# USB-Audio_ver_1_0.net
KiCad netlist of a schematic drawn in EAGLE
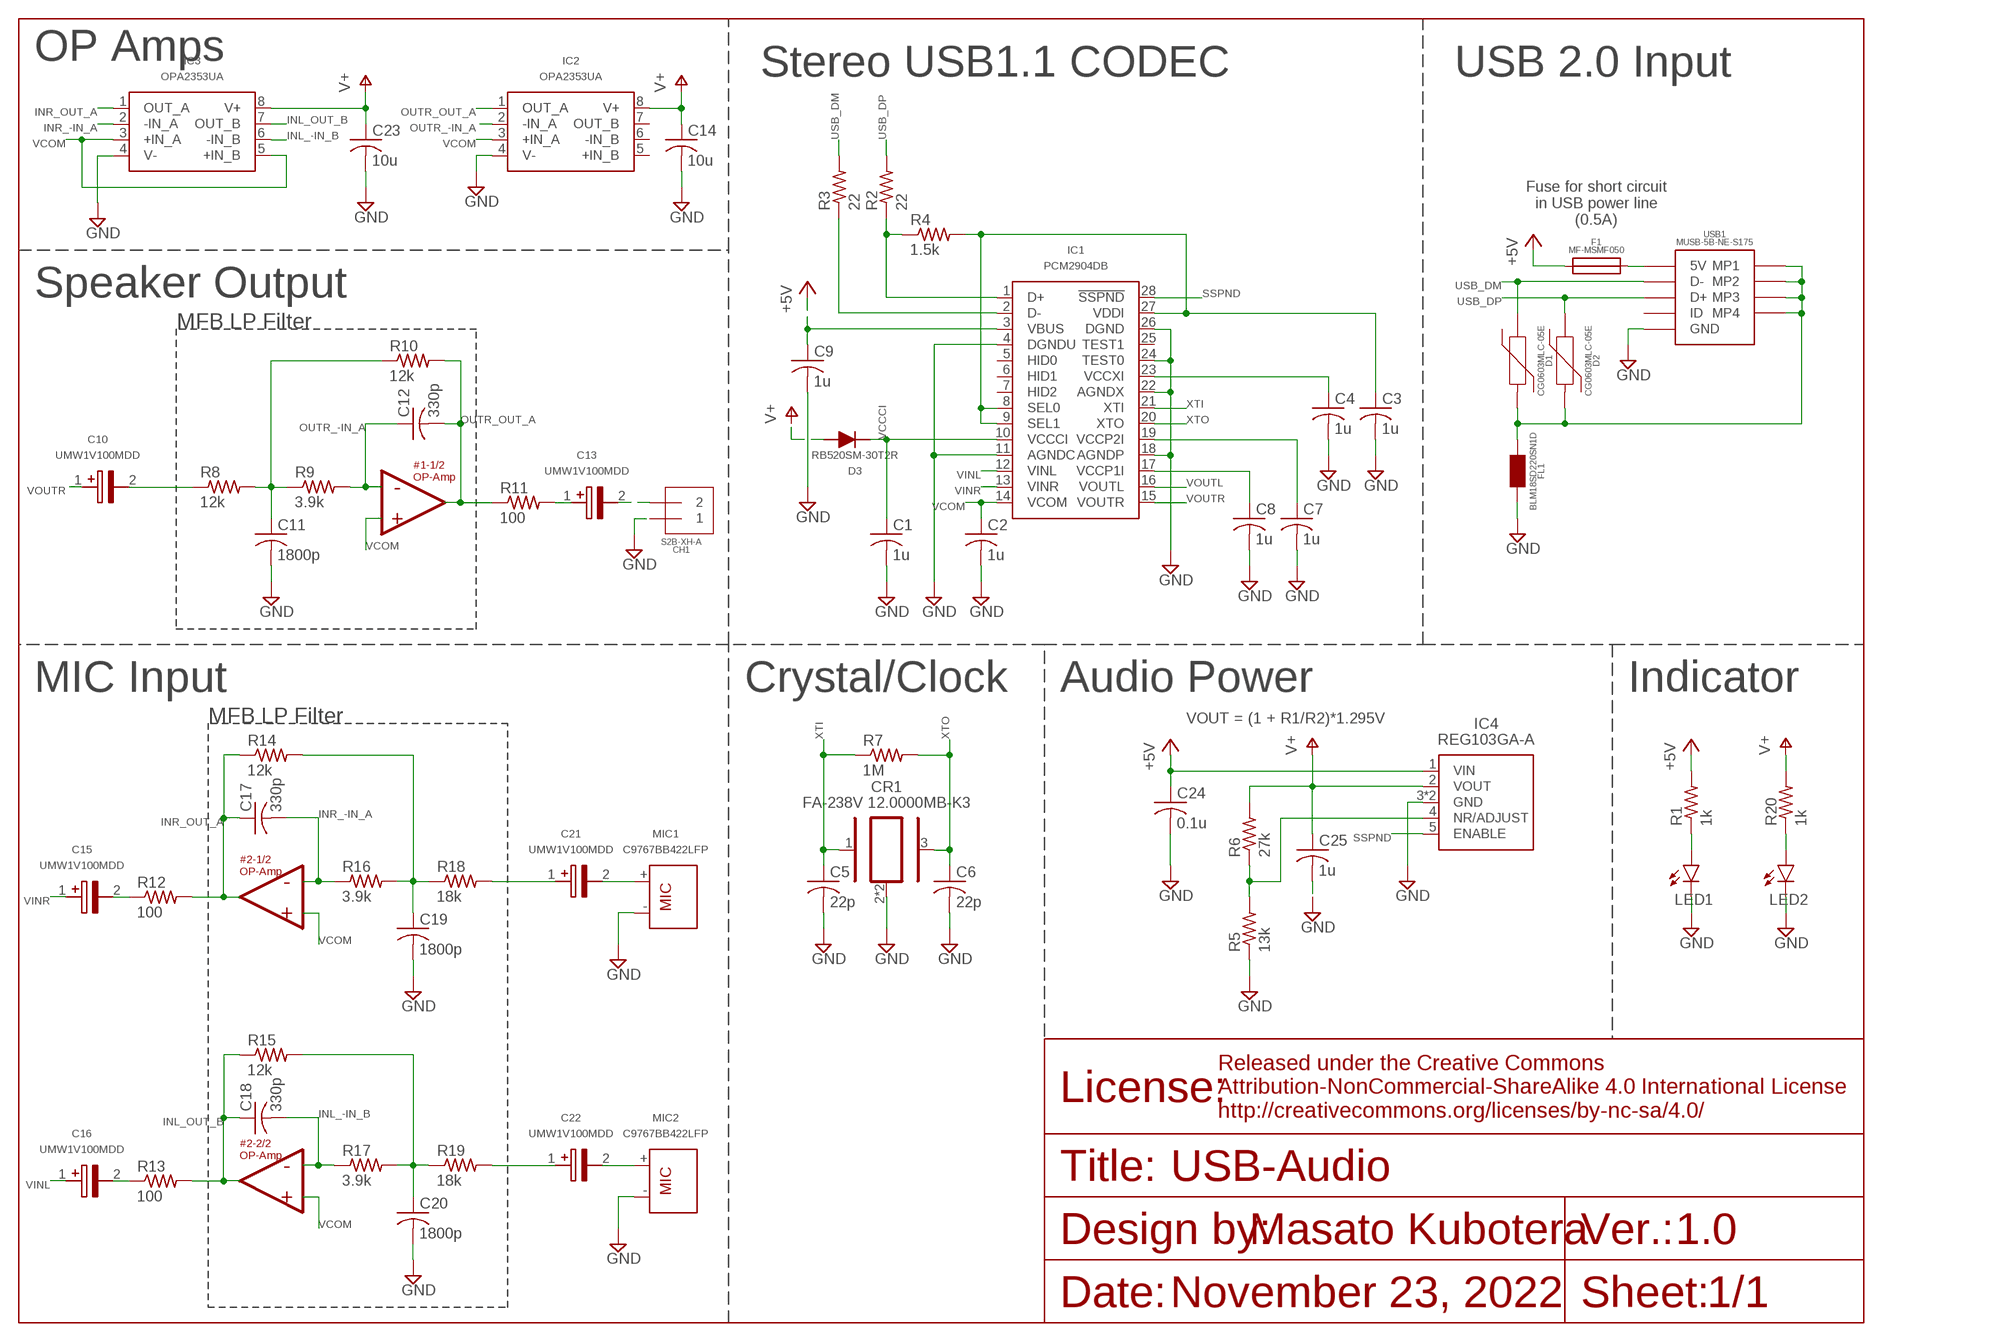
[diagram p0: schematic, sheet 1]

(export (version "E")
  (design (tool "Eeschema 10.0.6"))
  (components
    (comp (ref "C1")
      (value "1u")
      (footprint "eagle-import:C1608")
      (libsource (lib "eagle-import") (part "C-USC1608"))
    )
    (comp (ref "C2")
      (value "1u")
      (footprint "eagle-import:C1608")
      (libsource (lib "eagle-import") (part "C-USC1608"))
    )
    (comp (ref "C3")
      (value "1u")
      (footprint "eagle-import:C1608")
      (libsource (lib "eagle-import") (part "C-USC1608"))
    )
    (comp (ref "C4")
      (value "1u")
      (footprint "eagle-import:C1608")
      (libsource (lib "eagle-import") (part "C-USC1608"))
    )
    (comp (ref "C5")
      (value "22p")
      (footprint "eagle-import:C1608")
      (libsource (lib "eagle-import") (part "C-USC1608"))
    )
    (comp (ref "C6")
      (value "22p")
      (footprint "eagle-import:C1608")
      (libsource (lib "eagle-import") (part "C-USC1608"))
    )
    (comp (ref "C7")
      (value "1u")
      (footprint "eagle-import:C1608")
      (libsource (lib "eagle-import") (part "C-USC1608"))
    )
    (comp (ref "C8")
      (value "1u")
      (footprint "eagle-import:C1608")
      (libsource (lib "eagle-import") (part "C-USC1608"))
    )
    (comp (ref "C9")
      (value "1u")
      (footprint "eagle-import:C1608")
      (libsource (lib "eagle-import") (part "C-USC1608"))
    )
    (comp (ref "C10")
      (value "UMW1V100MDD")
      (footprint "eagle-import:UMW1V100MDD")
      (libsource (lib "eagle-import") (part "UMW1V100MDD"))
    )
    (comp (ref "C11")
      (value "1800p")
      (footprint "eagle-import:C1608")
      (libsource (lib "eagle-import") (part "C-USC1608"))
    )
    (comp (ref "C12")
      (value "330p")
      (footprint "eagle-import:C1608")
      (libsource (lib "eagle-import") (part "C-USC1608"))
    )
    (comp (ref "C13")
      (value "UMW1V100MDD")
      (footprint "eagle-import:UMW1V100MDD")
      (libsource (lib "eagle-import") (part "UMW1V100MDD"))
    )
    (comp (ref "C14")
      (value "10u")
      (footprint "eagle-import:C1608")
      (libsource (lib "eagle-import") (part "C-USC1608"))
    )
    (comp (ref "C15")
      (value "UMW1V100MDD")
      (footprint "eagle-import:UMW1V100MDD")
      (libsource (lib "eagle-import") (part "UMW1V100MDD"))
    )
    (comp (ref "C16")
      (value "UMW1V100MDD")
      (footprint "eagle-import:UMW1V100MDD")
      (libsource (lib "eagle-import") (part "UMW1V100MDD"))
    )
    (comp (ref "C17")
      (value "330p")
      (footprint "eagle-import:C1608")
      (libsource (lib "eagle-import") (part "C-USC1608"))
    )
    (comp (ref "C18")
      (value "330p")
      (footprint "eagle-import:C1608")
      (libsource (lib "eagle-import") (part "C-USC1608"))
    )
    (comp (ref "C19")
      (value "1800p")
      (footprint "eagle-import:C1608")
      (libsource (lib "eagle-import") (part "C-USC1608"))
    )
    (comp (ref "C20")
      (value "1800p")
      (footprint "eagle-import:C1608")
      (libsource (lib "eagle-import") (part "C-USC1608"))
    )
    (comp (ref "C21")
      (value "UMW1V100MDD")
      (footprint "eagle-import:UMW1V100MDD")
      (libsource (lib "eagle-import") (part "UMW1V100MDD"))
    )
    (comp (ref "C22")
      (value "UMW1V100MDD")
      (footprint "eagle-import:UMW1V100MDD")
      (libsource (lib "eagle-import") (part "UMW1V100MDD"))
    )
    (comp (ref "C23")
      (value "10u")
      (footprint "eagle-import:C1608")
      (libsource (lib "eagle-import") (part "C-USC1608"))
    )
    (comp (ref "C24")
      (value "0.1u")
      (footprint "eagle-import:C1608")
      (libsource (lib "eagle-import") (part "C-USC1608"))
    )
    (comp (ref "C25")
      (value "1u")
      (footprint "eagle-import:C1608")
      (libsource (lib "eagle-import") (part "C-USC1608"))
    )
    (comp (ref "CH1")
      (value "S2B-XH-A")
      (footprint "eagle-import:S2B-XH-A")
      (libsource (lib "eagle-import") (part "S2B-XH-A"))
    )
    (comp (ref "CR1")
      (value "FA-238V12.0000MB-K3")
      (footprint "eagle-import:FA238V")
      (libsource (lib "eagle-import") (part "FA-238V12.0000MB-K3"))
    )
    (comp (ref "D1")
      (value "CG0603MLC-05E")
      (footprint "eagle-import:CG0603MLC-05E")
      (libsource (lib "eagle-import") (part "CG0603MLC-05E"))
    )
    (comp (ref "D2")
      (value "CG0603MLC-05E")
      (footprint "eagle-import:CG0603MLC-05E")
      (libsource (lib "eagle-import") (part "CG0603MLC-05E"))
    )
    (comp (ref "D3")
      (value "RB520SM-30T2R")
      (footprint "eagle-import:SOD-523-2")
      (libsource (lib "eagle-import") (part "RB520SM-30T2R"))
    )
    (comp (ref "F1")
      (value "MF-MSMF050")
      (footprint "eagle-import:MF-MSMF050")
      (libsource (lib "eagle-import") (part "MF-MSMF050"))
    )
    (comp (ref "FL1")
      (value "BLM18SD220SN1D")
      (footprint "eagle-import:BLM18SD220SN1D")
      (libsource (lib "eagle-import") (part "BLM18SD220SN1D"))
    )
    (comp (ref "IC1")
      (value "PCM2904DB")
      (footprint "eagle-import:PCM2904DB")
      (libsource (lib "eagle-import") (part "PCM2904DB"))
    )
    (comp (ref "IC2")
      (value "OPA2353UA")
      (footprint "eagle-import:OPA2353UA")
      (libsource (lib "eagle-import") (part "OPA2353UA"))
    )
    (comp (ref "IC3")
      (value "OPA2353UA")
      (footprint "eagle-import:OPA2353UA")
      (libsource (lib "eagle-import") (part "OPA2353UA"))
    )
    (comp (ref "IC4")
      (value "REG103GA-A")
      (footprint "eagle-import:SOT223-5")
      (libsource (lib "eagle-import") (part "REG103GA-A"))
    )
    (comp (ref "LED1")
      (value "LEDSML0603")
      (footprint "eagle-import:SML0603")
      (libsource (lib "eagle-import") (part "LEDSML0603"))
    )
    (comp (ref "LED2")
      (value "LEDSML0603")
      (footprint "eagle-import:SML0603")
      (libsource (lib "eagle-import") (part "LEDSML0603"))
    )
    (comp (ref "MIC1")
      (value "C9767BB422LFP")
      (footprint "eagle-import:C9767BB422LFP")
      (libsource (lib "eagle-import") (part "C9767BB422LFP"))
    )
    (comp (ref "MIC2")
      (value "C9767BB422LFP")
      (footprint "eagle-import:C9767BB422LFP")
      (libsource (lib "eagle-import") (part "C9767BB422LFP"))
    )
    (comp (ref "R1")
      (value "1k")
      (footprint "eagle-import:R0603")
      (libsource (lib "eagle-import") (part "R-US_R0603"))
    )
    (comp (ref "R2")
      (value "22")
      (footprint "eagle-import:R0603")
      (libsource (lib "eagle-import") (part "R-US_R0603"))
    )
    (comp (ref "R3")
      (value "22")
      (footprint "eagle-import:R0603")
      (libsource (lib "eagle-import") (part "R-US_R0603"))
    )
    (comp (ref "R4")
      (value "1.5k")
      (footprint "eagle-import:R0603")
      (libsource (lib "eagle-import") (part "R-US_R0603"))
    )
    (comp (ref "R5")
      (value "13k")
      (footprint "eagle-import:R0603")
      (libsource (lib "eagle-import") (part "R-US_R0603"))
    )
    (comp (ref "R6")
      (value "27k")
      (footprint "eagle-import:R0603")
      (libsource (lib "eagle-import") (part "R-US_R0603"))
    )
    (comp (ref "R7")
      (value "1M")
      (footprint "eagle-import:R0603")
      (libsource (lib "eagle-import") (part "R-US_R0603"))
    )
    (comp (ref "R8")
      (value "12k")
      (footprint "eagle-import:R0603")
      (libsource (lib "eagle-import") (part "R-US_R0603"))
    )
    (comp (ref "R9")
      (value "3.9k")
      (footprint "eagle-import:R0603")
      (libsource (lib "eagle-import") (part "R-US_R0603"))
    )
    (comp (ref "R10")
      (value "12k")
      (footprint "eagle-import:R0603")
      (libsource (lib "eagle-import") (part "R-US_R0603"))
    )
    (comp (ref "R11")
      (value "100")
      (footprint "eagle-import:R0603")
      (libsource (lib "eagle-import") (part "R-US_R0603"))
    )
    (comp (ref "R12")
      (value "100")
      (footprint "eagle-import:R0603")
      (libsource (lib "eagle-import") (part "R-US_R0603"))
    )
    (comp (ref "R13")
      (value "100")
      (footprint "eagle-import:R0603")
      (libsource (lib "eagle-import") (part "R-US_R0603"))
    )
    (comp (ref "R14")
      (value "12k")
      (footprint "eagle-import:R0603")
      (libsource (lib "eagle-import") (part "R-US_R0603"))
    )
    (comp (ref "R15")
      (value "12k")
      (footprint "eagle-import:R0603")
      (libsource (lib "eagle-import") (part "R-US_R0603"))
    )
    (comp (ref "R16")
      (value "3.9k")
      (footprint "eagle-import:R0603")
      (libsource (lib "eagle-import") (part "R-US_R0603"))
    )
    (comp (ref "R17")
      (value "3.9k")
      (footprint "eagle-import:R0603")
      (libsource (lib "eagle-import") (part "R-US_R0603"))
    )
    (comp (ref "R18")
      (value "18k")
      (footprint "eagle-import:R0603")
      (libsource (lib "eagle-import") (part "R-US_R0603"))
    )
    (comp (ref "R19")
      (value "18k")
      (footprint "eagle-import:R0603")
      (libsource (lib "eagle-import") (part "R-US_R0603"))
    )
    (comp (ref "R20")
      (value "1k")
      (footprint "eagle-import:R0603")
      (libsource (lib "eagle-import") (part "R-US_R0603"))
    )
    (comp (ref "USB1")
      (value "MINI_USB_B_SMD")
      (footprint "eagle-import:MINI_USB_B_SMD")
      (libsource (lib "eagle-import") (part "MINI_USB_B_SMD"))
    )
  )
  (nets
    (net (code "1") (name "+5V") (class "Default")
      (node (ref "C24") (pin "1") (pinfunction "1_1") (pintype "passive"))
      (node (ref "C9") (pin "1") (pinfunction "1_1") (pintype "passive"))
      (node (ref "F1") (pin "1") (pinfunction "1_1") (pintype "bidirectional"))
      (node (ref "IC1") (pin "3") (pinfunction "VBUS_3") (pintype "bidirectional"))
      (node (ref "IC4") (pin "1") (pinfunction "VIN_1") (pintype "input"))
      (node (ref "R1") (pin "2") (pinfunction "2_2") (pintype "passive"))
    )
    (net (code "2") (name "/INL_-IN_B") (class "Default")
      (node (ref "C18") (pin "2") (pinfunction "2_2") (pintype "passive"))
      (node (ref "IC3") (pin "6") (pinfunction "-IN_B_6") (pintype "bidirectional"))
      (node (ref "R17") (pin "1") (pinfunction "1_1") (pintype "passive"))
    )
    (net (code "3") (name "/INL_OUT_B") (class "Default")
      (node (ref "C18") (pin "1") (pinfunction "1_1") (pintype "passive"))
      (node (ref "IC3") (pin "7") (pinfunction "OUT_B_7") (pintype "bidirectional"))
      (node (ref "R13") (pin "2") (pinfunction "2_2") (pintype "passive"))
      (node (ref "R15") (pin "1") (pinfunction "1_1") (pintype "passive"))
    )
    (net (code "4") (name "/INR_-IN_A") (class "Default")
      (node (ref "C17") (pin "2") (pinfunction "2_2") (pintype "passive"))
      (node (ref "IC3") (pin "2") (pinfunction "-IN_A_2") (pintype "bidirectional"))
      (node (ref "R16") (pin "1") (pinfunction "1_1") (pintype "passive"))
    )
    (net (code "5") (name "/INR_OUT_A") (class "Default")
      (node (ref "C17") (pin "1") (pinfunction "1_1") (pintype "passive"))
      (node (ref "IC3") (pin "1") (pinfunction "OUT_A_1") (pintype "bidirectional"))
      (node (ref "R12") (pin "2") (pinfunction "2_2") (pintype "passive"))
      (node (ref "R14") (pin "1") (pinfunction "1_1") (pintype "passive"))
    )
    (net (code "6") (name "/OUTR_-IN_A") (class "Default")
      (node (ref "C12") (pin "1") (pinfunction "1_1") (pintype "passive"))
      (node (ref "IC2") (pin "2") (pinfunction "-IN_A_2") (pintype "bidirectional"))
      (node (ref "R9") (pin "2") (pinfunction "2_2") (pintype "passive"))
    )
    (net (code "7") (name "/OUTR_OUT_A") (class "Default")
      (node (ref "C12") (pin "2") (pinfunction "2_2") (pintype "passive"))
      (node (ref "IC2") (pin "1") (pinfunction "OUT_A_1") (pintype "bidirectional"))
      (node (ref "R10") (pin "2") (pinfunction "2_2") (pintype "passive"))
      (node (ref "R11") (pin "1") (pinfunction "1_1") (pintype "passive"))
    )
    (net (code "8") (name "/SSPND") (class "Default")
      (node (ref "C8") (pin "1") (pinfunction "1_1") (pintype "passive"))
      (node (ref "IC1") (pin "17") (pinfunction "VCCP1I_17") (pintype "bidirectional"))
      (node (ref "IC1") (pin "28") (pinfunction "~{SSPND}_28") (pintype "bidirectional"))
      (node (ref "IC4") (pin "5") (pinfunction "ENABLE_5") (pintype "bidirectional"))
    )
    (net (code "9") (name "/USB_DM") (class "Default")
      (node (ref "D1") (pin "1") (pinfunction "1_1") (pintype "bidirectional"))
      (node (ref "R3") (pin "2") (pinfunction "2_2") (pintype "passive"))
      (node (ref "USB1") (pin "2") (pinfunction "D-_2") (pintype "bidirectional"))
    )
    (net (code "10") (name "/USB_DP") (class "Default")
      (node (ref "D2") (pin "1") (pinfunction "1_1") (pintype "bidirectional"))
      (node (ref "R2") (pin "2") (pinfunction "2_2") (pintype "passive"))
      (node (ref "USB1") (pin "3") (pinfunction "D+_3") (pintype "bidirectional"))
    )
    (net (code "11") (name "/VCCCI") (class "Default")
      (node (ref "C1") (pin "1") (pinfunction "1_1") (pintype "passive"))
      (node (ref "D3") (pin "1") (pinfunction "K_1") (pintype "bidirectional"))
      (node (ref "IC1") (pin "10") (pinfunction "VCCCI_10") (pintype "bidirectional"))
    )
    (net (code "12") (name "/VCOM") (class "Default")
      (node (ref "C2") (pin "1") (pinfunction "1_1") (pintype "passive"))
      (node (ref "IC1") (pin "14") (pinfunction "VCOM_14") (pintype "bidirectional"))
      (node (ref "IC2") (pin "3") (pinfunction "+IN_A_3") (pintype "bidirectional"))
      (node (ref "IC3") (pin "3") (pinfunction "+IN_A_3") (pintype "bidirectional"))
      (node (ref "IC3") (pin "5") (pinfunction "+IN_B_5") (pintype "bidirectional"))
    )
    (net (code "13") (name "/VINL") (class "Default")
      (node (ref "C16") (pin "1") (pinfunction "+_1") (pintype "bidirectional"))
      (node (ref "IC1") (pin "12") (pinfunction "VINL_12") (pintype "bidirectional"))
    )
    (net (code "14") (name "/VINR") (class "Default")
      (node (ref "C15") (pin "1") (pinfunction "+_1") (pintype "bidirectional"))
      (node (ref "IC1") (pin "13") (pinfunction "VINR_13") (pintype "bidirectional"))
    )
    (net (code "15") (name "/VOUTL") (class "Default")
      (node (ref "IC1") (pin "16") (pinfunction "VOUTL_16") (pintype "bidirectional"))
    )
    (net (code "16") (name "/VOUTR") (class "Default")
      (node (ref "C10") (pin "1") (pinfunction "+_1") (pintype "bidirectional"))
      (node (ref "IC1") (pin "15") (pinfunction "VOUTR_15") (pintype "bidirectional"))
    )
    (net (code "17") (name "/XTI") (class "Default")
      (node (ref "C5") (pin "1") (pinfunction "1_1") (pintype "passive"))
      (node (ref "CR1") (pin "1") (pinfunction "P$1_1") (pintype "bidirectional"))
      (node (ref "IC1") (pin "21") (pinfunction "XTI_21") (pintype "bidirectional"))
      (node (ref "R7") (pin "1") (pinfunction "1_1") (pintype "passive"))
    )
    (net (code "18") (name "/XTO") (class "Default")
      (node (ref "C6") (pin "1") (pinfunction "1_1") (pintype "passive"))
      (node (ref "CR1") (pin "3") (pinfunction "P$2_3") (pintype "bidirectional"))
      (node (ref "IC1") (pin "20") (pinfunction "XTO_20") (pintype "bidirectional"))
      (node (ref "R7") (pin "2") (pinfunction "2_2") (pintype "passive"))
    )
    (net (code "19") (name "GND") (class "Default")
      (node (ref "C1") (pin "2") (pinfunction "2_2") (pintype "passive"))
      (node (ref "C11") (pin "2") (pinfunction "2_2") (pintype "passive"))
      (node (ref "C14") (pin "2") (pinfunction "2_2") (pintype "passive"))
      (node (ref "C19") (pin "2") (pinfunction "2_2") (pintype "passive"))
      (node (ref "C2") (pin "2") (pinfunction "2_2") (pintype "passive"))
      (node (ref "C20") (pin "2") (pinfunction "2_2") (pintype "passive"))
      (node (ref "C23") (pin "2") (pinfunction "2_2") (pintype "passive"))
      (node (ref "C24") (pin "2") (pinfunction "2_2") (pintype "passive"))
      (node (ref "C25") (pin "2") (pinfunction "2_2") (pintype "passive"))
      (node (ref "C3") (pin "2") (pinfunction "2_2") (pintype "passive"))
      (node (ref "C4") (pin "2") (pinfunction "2_2") (pintype "passive"))
      (node (ref "C5") (pin "2") (pinfunction "2_2") (pintype "passive"))
      (node (ref "C6") (pin "2") (pinfunction "2_2") (pintype "passive"))
      (node (ref "C7") (pin "2") (pinfunction "2_2") (pintype "passive"))
      (node (ref "C8") (pin "2") (pinfunction "2_2") (pintype "passive"))
      (node (ref "C9") (pin "2") (pinfunction "2_2") (pintype "passive"))
      (node (ref "CH1") (pin "1") (pinfunction "1_1") (pintype "bidirectional"))
      (node (ref "CR1") (pin "2") (pinfunction "P$3_2") (pintype "bidirectional"))
      (node (ref "CR1") (pin "4") (pinfunction "P$3_4") (pintype "bidirectional"))
      (node (ref "FL1") (pin "2") (pinfunction "2_2") (pintype "bidirectional"))
      (node (ref "IC1") (pin "11") (pinfunction "AGNDC_11") (pintype "bidirectional"))
      (node (ref "IC1") (pin "18") (pinfunction "AGNDP_18") (pintype "bidirectional"))
      (node (ref "IC1") (pin "22") (pinfunction "AGNDX_22") (pintype "bidirectional"))
      (node (ref "IC1") (pin "24") (pinfunction "TEST0_24") (pintype "bidirectional"))
      (node (ref "IC1") (pin "26") (pinfunction "DGND_26") (pintype "bidirectional"))
      (node (ref "IC1") (pin "4") (pinfunction "DGNDU_4") (pintype "bidirectional"))
      (node (ref "IC2") (pin "4") (pinfunction "V-_4") (pintype "bidirectional"))
      (node (ref "IC3") (pin "4") (pinfunction "V-_4") (pintype "bidirectional"))
      (node (ref "IC4") (pin "3") (pinfunction "GND_3") (pintype "power_in"))
      (node (ref "IC4") (pin "6") (pinfunction "GND_6") (pintype "power_in"))
      (node (ref "LED1") (pin "C") (pinfunction "C_C") (pintype "passive"))
      (node (ref "LED2") (pin "C") (pinfunction "C_C") (pintype "passive"))
      (node (ref "MIC1") (pin "-") (pinfunction "-_-") (pintype "bidirectional"))
      (node (ref "MIC2") (pin "-") (pinfunction "-_-") (pintype "bidirectional"))
      (node (ref "R5") (pin "1") (pinfunction "1_1") (pintype "passive"))
      (node (ref "USB1") (pin "5") (pinfunction "GND_5") (pintype "bidirectional"))
    )
    (net (code "20") (name "Net-(C10--)") (class "Default")
      (node (ref "C10") (pin "2") (pinfunction "-_2") (pintype "bidirectional"))
      (node (ref "R8") (pin "1") (pinfunction "1_1") (pintype "passive"))
    )
    (net (code "21") (name "Net-(C11-Pad1)") (class "Default")
      (node (ref "C11") (pin "1") (pinfunction "1_1") (pintype "passive"))
      (node (ref "R10") (pin "1") (pinfunction "1_1") (pintype "passive"))
      (node (ref "R8") (pin "2") (pinfunction "2_2") (pintype "passive"))
      (node (ref "R9") (pin "1") (pinfunction "1_1") (pintype "passive"))
    )
    (net (code "22") (name "Net-(C13-+)") (class "Default")
      (node (ref "C13") (pin "1") (pinfunction "+_1") (pintype "bidirectional"))
      (node (ref "R11") (pin "2") (pinfunction "2_2") (pintype "passive"))
    )
    (net (code "23") (name "Net-(C13--)") (class "Default")
      (node (ref "C13") (pin "2") (pinfunction "-_2") (pintype "bidirectional"))
      (node (ref "CH1") (pin "2") (pinfunction "2_2") (pintype "bidirectional"))
    )
    (net (code "24") (name "Net-(C15--)") (class "Default")
      (node (ref "C15") (pin "2") (pinfunction "-_2") (pintype "bidirectional"))
      (node (ref "R12") (pin "1") (pinfunction "1_1") (pintype "passive"))
    )
    (net (code "25") (name "Net-(C16--)") (class "Default")
      (node (ref "C16") (pin "2") (pinfunction "-_2") (pintype "bidirectional"))
      (node (ref "R13") (pin "1") (pinfunction "1_1") (pintype "passive"))
    )
    (net (code "26") (name "Net-(C19-Pad1)") (class "Default")
      (node (ref "C19") (pin "1") (pinfunction "1_1") (pintype "passive"))
      (node (ref "R14") (pin "2") (pinfunction "2_2") (pintype "passive"))
      (node (ref "R16") (pin "2") (pinfunction "2_2") (pintype "passive"))
      (node (ref "R18") (pin "1") (pinfunction "1_1") (pintype "passive"))
    )
    (net (code "27") (name "Net-(C20-Pad1)") (class "Default")
      (node (ref "C20") (pin "1") (pinfunction "1_1") (pintype "passive"))
      (node (ref "R15") (pin "2") (pinfunction "2_2") (pintype "passive"))
      (node (ref "R17") (pin "2") (pinfunction "2_2") (pintype "passive"))
      (node (ref "R19") (pin "1") (pinfunction "1_1") (pintype "passive"))
    )
    (net (code "28") (name "Net-(C21-+)") (class "Default")
      (node (ref "C21") (pin "1") (pinfunction "+_1") (pintype "bidirectional"))
      (node (ref "R18") (pin "2") (pinfunction "2_2") (pintype "passive"))
    )
    (net (code "29") (name "Net-(C21--)") (class "Default")
      (node (ref "C21") (pin "2") (pinfunction "-_2") (pintype "bidirectional"))
      (node (ref "MIC1") (pin "+") (pinfunction "+_+") (pintype "bidirectional"))
    )
    (net (code "30") (name "Net-(C22-+)") (class "Default")
      (node (ref "C22") (pin "1") (pinfunction "+_1") (pintype "bidirectional"))
      (node (ref "R19") (pin "2") (pinfunction "2_2") (pintype "passive"))
    )
    (net (code "31") (name "Net-(C22--)") (class "Default")
      (node (ref "C22") (pin "2") (pinfunction "-_2") (pintype "bidirectional"))
      (node (ref "MIC2") (pin "+") (pinfunction "+_+") (pintype "bidirectional"))
    )
    (net (code "32") (name "Net-(D1-Pad2)") (class "Default")
      (node (ref "D1") (pin "2") (pinfunction "2_2") (pintype "bidirectional"))
      (node (ref "D2") (pin "2") (pinfunction "2_2") (pintype "bidirectional"))
      (node (ref "FL1") (pin "1") (pinfunction "1_1") (pintype "bidirectional"))
      (node (ref "USB1") (pin "MP1") (pinfunction "MP1_MP1") (pintype "bidirectional"))
      (node (ref "USB1") (pin "MP2") (pinfunction "MP2_MP2") (pintype "bidirectional"))
      (node (ref "USB1") (pin "MP3") (pinfunction "MP3_MP3") (pintype "bidirectional"))
      (node (ref "USB1") (pin "MP4") (pinfunction "MP4_MP4") (pintype "bidirectional"))
    )
    (net (code "33") (name "Net-(IC1-D+)") (class "Default")
      (node (ref "IC1") (pin "1") (pinfunction "D+_1") (pintype "bidirectional"))
      (node (ref "R2") (pin "1") (pinfunction "1_1") (pintype "passive"))
      (node (ref "R4") (pin "1") (pinfunction "1_1") (pintype "passive"))
    )
    (net (code "34") (name "Net-(IC1-D-)") (class "Default")
      (node (ref "IC1") (pin "2") (pinfunction "D-_2") (pintype "bidirectional"))
      (node (ref "R3") (pin "1") (pinfunction "1_1") (pintype "passive"))
    )
    (net (code "35") (name "Net-(IC1-SEL0)") (class "Default")
      (node (ref "C3") (pin "1") (pinfunction "1_1") (pintype "passive"))
      (node (ref "IC1") (pin "27") (pinfunction "VDDI_27") (pintype "bidirectional"))
      (node (ref "IC1") (pin "8") (pinfunction "SEL0_8") (pintype "bidirectional"))
      (node (ref "IC1") (pin "9") (pinfunction "SEL1_9") (pintype "bidirectional"))
      (node (ref "R4") (pin "2") (pinfunction "2_2") (pintype "passive"))
    )
    (net (code "36") (name "Net-(IC1-VCCP2I)") (class "Default")
      (node (ref "C7") (pin "1") (pinfunction "1_1") (pintype "passive"))
      (node (ref "IC1") (pin "19") (pinfunction "VCCP2I_19") (pintype "bidirectional"))
    )
    (net (code "37") (name "Net-(IC1-VCCXI)") (class "Default")
      (node (ref "C4") (pin "1") (pinfunction "1_1") (pintype "passive"))
      (node (ref "IC1") (pin "23") (pinfunction "VCCXI_23") (pintype "bidirectional"))
    )
    (net (code "38") (name "Net-(IC4-NR{slash}ADJUST)") (class "Default")
      (node (ref "IC4") (pin "4") (pinfunction "NR/ADJUST_4") (pintype "bidirectional"))
      (node (ref "R5") (pin "2") (pinfunction "2_2") (pintype "passive"))
      (node (ref "R6") (pin "1") (pinfunction "1_1") (pintype "passive"))
    )
    (net (code "39") (name "Net-(LED1-PadA)") (class "Default")
      (node (ref "LED1") (pin "A") (pinfunction "A_A") (pintype "passive"))
      (node (ref "R1") (pin "1") (pinfunction "1_1") (pintype "passive"))
    )
    (net (code "40") (name "Net-(LED2-PadA)") (class "Default")
      (node (ref "LED2") (pin "A") (pinfunction "A_A") (pintype "passive"))
      (node (ref "R20") (pin "1") (pinfunction "1_1") (pintype "passive"))
    )
    (net (code "41") (name "Net-(USB1-5V)") (class "Default")
      (node (ref "F1") (pin "2") (pinfunction "2_2") (pintype "bidirectional"))
      (node (ref "USB1") (pin "1") (pinfunction "5V_1") (pintype "bidirectional"))
    )
    (net (code "42") (name "V+") (class "Default")
      (node (ref "C14") (pin "1") (pinfunction "1_1") (pintype "passive"))
      (node (ref "C23") (pin "1") (pinfunction "1_1") (pintype "passive"))
      (node (ref "C25") (pin "1") (pinfunction "1_1") (pintype "passive"))
      (node (ref "D3") (pin "2") (pinfunction "A_2") (pintype "bidirectional"))
      (node (ref "IC2") (pin "8") (pinfunction "V+_8") (pintype "bidirectional"))
      (node (ref "IC3") (pin "8") (pinfunction "V+_8") (pintype "bidirectional"))
      (node (ref "IC4") (pin "2") (pinfunction "VOUT_2") (pintype "output"))
      (node (ref "R20") (pin "2") (pinfunction "2_2") (pintype "passive"))
      (node (ref "R6") (pin "2") (pinfunction "2_2") (pintype "passive"))
    )
    (net (code "43") (name "unconnected-(IC1-HID0-Pad5)") (class "Default")
      (node (ref "IC1") (pin "5") (pinfunction "HID0_5") (pintype "bidirectional"))
    )
    (net (code "44") (name "unconnected-(IC1-HID1-Pad6)") (class "Default")
      (node (ref "IC1") (pin "6") (pinfunction "HID1_6") (pintype "bidirectional"))
    )
    (net (code "45") (name "unconnected-(IC1-HID2-Pad7)") (class "Default")
      (node (ref "IC1") (pin "7") (pinfunction "HID2_7") (pintype "bidirectional"))
    )
    (net (code "46") (name "unconnected-(IC1-TEST1-Pad25)") (class "Default")
      (node (ref "IC1") (pin "25") (pinfunction "TEST1_25") (pintype "bidirectional"))
    )
    (net (code "47") (name "unconnected-(IC2-+IN_B-Pad5)") (class "Default")
      (node (ref "IC2") (pin "5") (pinfunction "+IN_B_5") (pintype "bidirectional"))
    )
    (net (code "48") (name "unconnected-(IC2--IN_B-Pad6)") (class "Default")
      (node (ref "IC2") (pin "6") (pinfunction "-IN_B_6") (pintype "bidirectional"))
    )
    (net (code "49") (name "unconnected-(IC2-OUT_B-Pad7)") (class "Default")
      (node (ref "IC2") (pin "7") (pinfunction "OUT_B_7") (pintype "bidirectional"))
    )
    (net (code "50") (name "unconnected-(USB1-ID-Pad4)") (class "Default")
      (node (ref "USB1") (pin "4") (pinfunction "ID_4") (pintype "bidirectional"))
    )
  )
)
